# RC522_RFID.net
KiCad netlist of a schematic drawn in Altium Designer
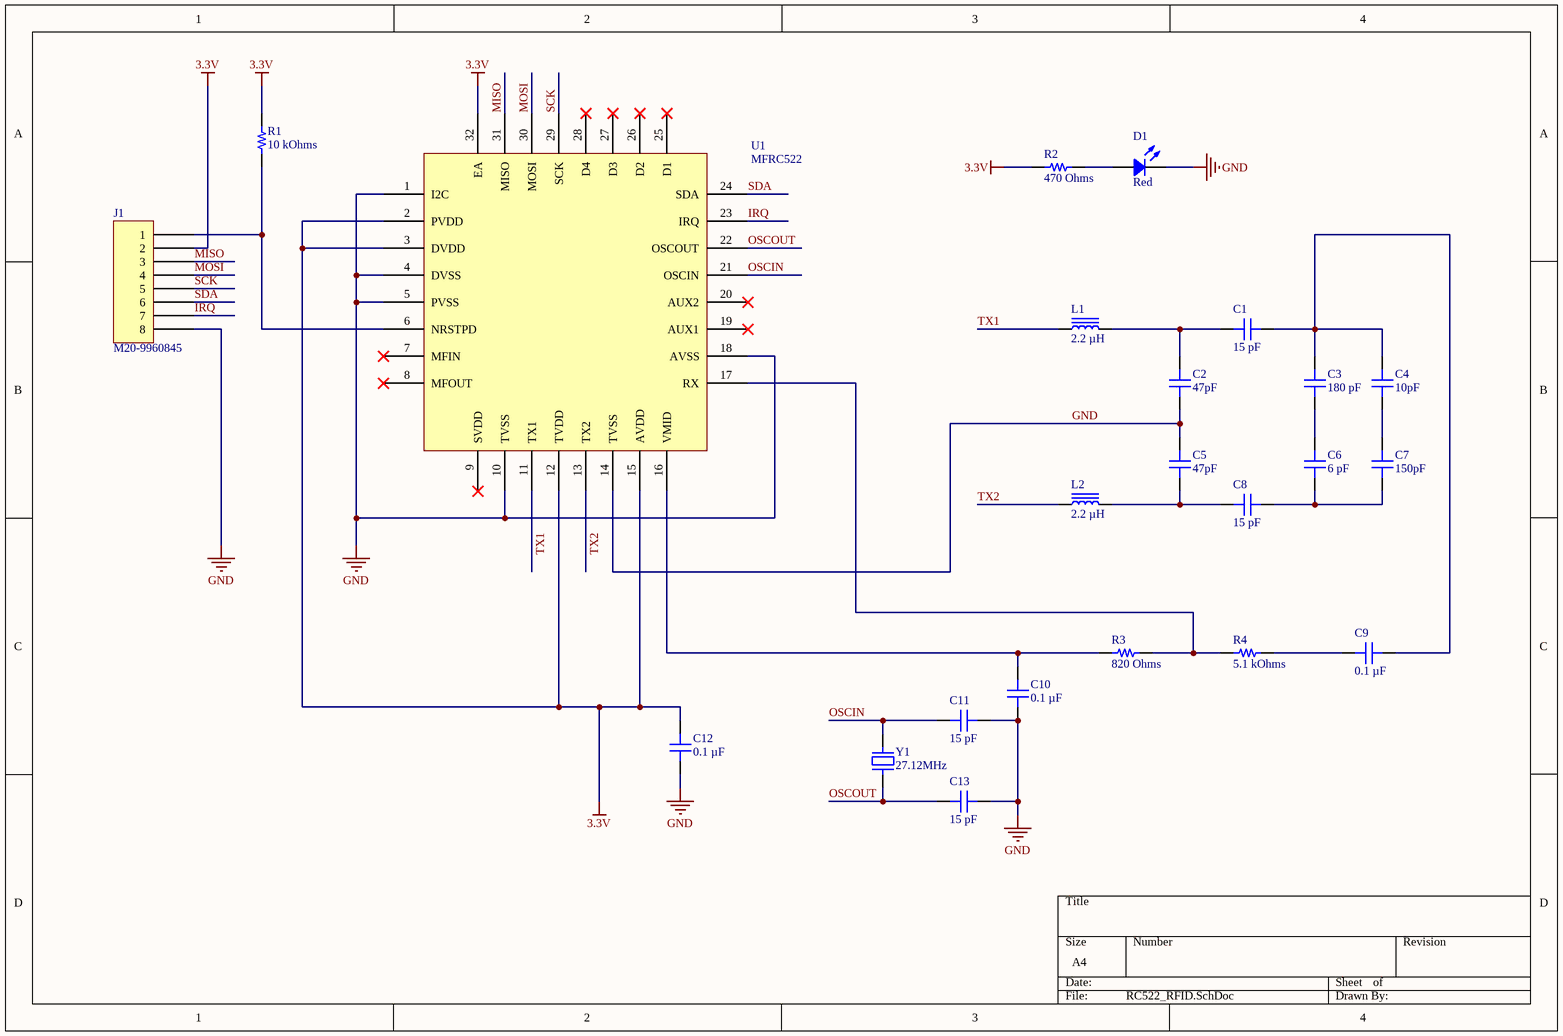
[diagram p0: RC522_RFID.SchDoc]

(export (version "E")
  (design (tool "Eeschema 10.0.6"))
  (components
    (comp (ref "C1")
      (value "15 pF")
      (footprint "CAP 0805_2012")
      (description "CAP CER 15PF 25V C0G/NP0 0805")
      (fields
        (field (name "PART NUMBER") "885012007029")
        (field (name "CAPACITANCE") "15 pF")
        (field (name "MANUFACTURER") "Würth Elektronik")
      )
      (libsource (lib "Celestial Altium Library - altium_library") (part "Capacitor"))
    )
    (comp (ref "C2")
      (value "47pF")
      (footprint "CAP 0805_2012")
      (description "CAP CER 47PF 50V C0G/NP0 0805")
      (fields
        (field (name "PART NUMBER") "08055A470KAT2A")
        (field (name "CAPACITANCE") "47pF")
        (field (name "MANUFACTURER") "AVX Corporation")
      )
      (libsource (lib "Celestial Altium Library - altium_library") (part "Capacitor"))
    )
    (comp (ref "C3")
      (value "180 pF")
      (footprint "CAP 0805_2012")
      (description "CAP CER 180PF 50V X7R 0805")
      (fields
        (field (name "PART NUMBER") "VJ0805Y181KXAPW1BC")
        (field (name "CAPACITANCE") "180 pF")
        (field (name "MANUFACTURER") "Vishay Vitramon")
      )
      (libsource (lib "Celestial Altium Library - altium_library") (part "Capacitor"))
    )
    (comp (ref "C4")
      (value "10pF")
      (footprint "CAP 0805_2012")
      (description "CAP CER 10PF 50V X7R 0805")
      (fields
        (field (name "PART NUMBER") "08055C100KAT2A")
        (field (name "CAPACITANCE") "10pF")
        (field (name "MANUFACTURER") "AVX Corporation")
      )
      (libsource (lib "Celestial Altium Library - altium_library") (part "Capacitor"))
    )
    (comp (ref "C5")
      (value "47pF")
      (footprint "CAP 0805_2012")
      (description "CAP CER 47PF 50V C0G/NP0 0805")
      (fields
        (field (name "PART NUMBER") "08055A470KAT2A")
        (field (name "CAPACITANCE") "47pF")
        (field (name "MANUFACTURER") "AVX Corporation")
      )
      (libsource (lib "Celestial Altium Library - altium_library") (part "Capacitor"))
    )
    (comp (ref "C6")
      (value "6 pF")
      (footprint "CAP 0805_2012")
      (description "CAP CER 6PF 50V C0G/NPO 0805")
      (fields
        (field (name "PART NUMBER") "CC0805DRNPO9BN6R0")
        (field (name "CAPACITANCE") "6 pF")
        (field (name "MANUFACTURER") "Yageo")
      )
      (libsource (lib "Celestial Altium Library - altium_library") (part "Capacitor"))
    )
    (comp (ref "C7")
      (value "150pF")
      (footprint "CAP 0805_2012")
      (description "CAP CER 150PF 50V X7R 0805")
      (fields
        (field (name "PART NUMBER") "08055C151KAT2A")
        (field (name "CAPACITANCE") "150pF")
        (field (name "MANUFACTURER") "AVX Corporation")
      )
      (libsource (lib "Celestial Altium Library - altium_library") (part "Capacitor"))
    )
    (comp (ref "C8")
      (value "15 pF")
      (footprint "CAP 0805_2012")
      (description "CAP CER 15PF 25V C0G/NP0 0805")
      (fields
        (field (name "PART NUMBER") "885012007029")
        (field (name "CAPACITANCE") "15 pF")
        (field (name "MANUFACTURER") "Würth Elektronik")
      )
      (libsource (lib "Celestial Altium Library - altium_library") (part "Capacitor"))
    )
    (comp (ref "C9")
      (value "0.1 µF")
      (footprint "CAP 0805_2012")
      (description "CAP CER 0.1UF 25V X7R 0805")
      (fields
        (field (name "PART NUMBER") "VJ0805Y104KXXCW1BC")
        (field (name "CAPACITANCE") "0.1 µF")
        (field (name "MANUFACTURER") "Vishay Vitramon")
      )
      (libsource (lib "Celestial Altium Library - altium_library") (part "Capacitor"))
    )
    (comp (ref "C10")
      (value "0.1 µF")
      (footprint "CAP 0805_2012")
      (description "CAP CER 0.1UF 25V X7R 0805")
      (fields
        (field (name "PART NUMBER") "VJ0805Y104KXXCW1BC")
        (field (name "CAPACITANCE") "0.1 µF")
        (field (name "MANUFACTURER") "Vishay Vitramon")
      )
      (libsource (lib "Celestial Altium Library - altium_library") (part "Capacitor"))
    )
    (comp (ref "C11")
      (value "15 pF")
      (footprint "CAP 0805_2012")
      (description "CAP CER 15PF 25V C0G/NP0 0805")
      (fields
        (field (name "PART NUMBER") "885012007029")
        (field (name "CAPACITANCE") "15 pF")
        (field (name "MANUFACTURER") "Würth Elektronik")
      )
      (libsource (lib "Celestial Altium Library - altium_library") (part "Capacitor"))
    )
    (comp (ref "C12")
      (value "0.1 µF")
      (footprint "CAP 0805_2012")
      (description "CAP CER 0.1UF 25V X7R 0805")
      (fields
        (field (name "PART NUMBER") "VJ0805Y104KXXCW1BC")
        (field (name "CAPACITANCE") "0.1 µF")
        (field (name "MANUFACTURER") "Vishay Vitramon")
      )
      (libsource (lib "Celestial Altium Library - altium_library") (part "Capacitor"))
    )
    (comp (ref "C13")
      (value "15 pF")
      (footprint "CAP 0805_2012")
      (description "CAP CER 15PF 25V C0G/NP0 0805")
      (fields
        (field (name "PART NUMBER") "885012007029")
        (field (name "CAPACITANCE") "15 pF")
        (field (name "MANUFACTURER") "Würth Elektronik")
      )
      (libsource (lib "Celestial Altium Library - altium_library") (part "Capacitor"))
    )
    (comp (ref "D1")
      (value "Red")
      (footprint "LED 0805_2012 RED")
      (description "LED RED CLEAR 0805 SMD")
      (fields (field (name "PART NUMBER") "5988120107F") (field (name "MANUFACTURER") "Dialight"))
      (libsource (lib "Celestial Altium Library - altium_library") (part "LED"))
    )
    (comp (ref "J1")
      (value "M20-9960845")
      (footprint "HARWIN M20-9960845")
      (description "CONN HEADER R/A 8POS 2.54MM")
      (fields (field (name "MANUFACTURER") "Harwin Inc."))
      (libsource (lib "Celestial Altium Library - altium_library") (part "8 Pin"))
    )
    (comp (ref "L1")
      (value "2.2 µH")
      (footprint "IND 0806_2016")
      (description "FIXED IND 2.2UH 2A 138 MOHM SMD")
      (fields
        (field (name "PART NUMBER") "WPN201610U2R2MTY01")
        (field (name "MANUFACTURER") "Shenzhen Sunlord Electronics Co., Ltd.")
      )
      (libsource (lib "Celestial Altium Library - altium_library") (part "Inductor"))
    )
    (comp (ref "L2")
      (value "2.2 µH")
      (footprint "IND 0806_2016")
      (description "FIXED IND 2.2UH 2A 138 MOHM SMD")
      (fields
        (field (name "PART NUMBER") "WPN201610U2R2MTY01")
        (field (name "MANUFACTURER") "Shenzhen Sunlord Electronics Co., Ltd.")
      )
      (libsource (lib "Celestial Altium Library - altium_library") (part "Inductor"))
    )
    (comp (ref "R1")
      (value "10 kOhms")
      (footprint "RES 0805_2012")
      (description "RES 10K OHM 1% 1/2W 0805")
      (fields (field (name "PART NUMBER") "SDR10EZPF1002") (field (name "MANUFACTURER") "Rohm Semiconductor"))
      (libsource (lib "Celestial Altium Library - altium_library") (part "Resistor"))
    )
    (comp (ref "R2")
      (value "470 Ohms")
      (footprint "YAGEO RES RK73 RS73 SG73 0805_2012")
      (description "RES 470 OHM 1% 1/2W 0805")
      (fields
        (field (name "PART NUMBER") "SG73P2ATTD4700F")
        (field (name "MANUFACTURER") "KOA Speer Electronics, Inc.")
      )
      (libsource (lib "Celestial Altium Library - altium_library") (part "Resistor"))
    )
    (comp (ref "R3")
      (value "820 Ohms")
      (footprint "YAGEO RES 0805_2012")
      (description "RES 820 OHM 1% 1/2W 0805")
      (fields (field (name "PART NUMBER") "SR0805FR-47820RL") (field (name "MANUFACTURER") "Yageo"))
      (libsource (lib "Celestial Altium Library - altium_library") (part "Resistor"))
    )
    (comp (ref "R4")
      (value "5.1 kOhms")
      (footprint "YAGEO RES RK73 RS73 SG73 0805_2012")
      (description "RES 5.1K OHM 1% 1/2W 0805")
      (fields
        (field (name "PART NUMBER") "SG73P2ATTD5101F")
        (field (name "MANUFACTURER") "KOA Speer Electronics, Inc.")
      )
      (libsource (lib "Celestial Altium Library - altium_library") (part "Resistor"))
    )
    (comp (ref "U1") (value "MFRC522") (footprint "MFRC522") (libsource (lib "RC522_RFID") (part "MFRC522")))
    (comp (ref "Y1")
      (value "27.12MHz")
      (footprint "TXC 9C")
      (description "CRYSTAL 27.1200MHZ 18PF SMD")
      (fields (field (name "PART NUMBER") "9C-27.120MAAJ-T") (field (name "MANUFACTURER") "TXC CORPORATION"))
      (libsource (lib "Celestial Altium Library - altium_library") (part "TXC Crystal 9C"))
    )
  )
  (nets
    (net (code "1") (name "/IRQ") (class "Default")
      (node (ref "J1") (pin "7") (pinfunction "7_7") (pintype "passive"))
      (node (ref "U1") (pin "23") (pinfunction "IRQ_23") (pintype "passive"))
    )
    (net (code "2") (name "/MISO") (class "Default")
      (node (ref "J1") (pin "3") (pinfunction "3_3") (pintype "passive"))
      (node (ref "U1") (pin "31") (pinfunction "MISO_31") (pintype "passive"))
    )
    (net (code "3") (name "/MOSI") (class "Default")
      (node (ref "J1") (pin "4") (pinfunction "4_4") (pintype "passive"))
      (node (ref "U1") (pin "30") (pinfunction "MOSI_30") (pintype "passive"))
    )
    (net (code "4") (name "/OSCIN") (class "Default")
      (node (ref "C11") (pin "2") (pinfunction "2_2") (pintype "passive"))
      (node (ref "U1") (pin "21") (pinfunction "OSCIN_21") (pintype "passive"))
      (node (ref "Y1") (pin "2") (pinfunction "2_2") (pintype "passive"))
    )
    (net (code "5") (name "/OSCOUT") (class "Default")
      (node (ref "C13") (pin "1") (pinfunction "1_1") (pintype "passive"))
      (node (ref "U1") (pin "22") (pinfunction "OSCOUT_22") (pintype "passive"))
      (node (ref "Y1") (pin "1") (pinfunction "1_1") (pintype "passive"))
    )
    (net (code "6") (name "/SCK") (class "Default")
      (node (ref "J1") (pin "5") (pinfunction "5_5") (pintype "passive"))
      (node (ref "U1") (pin "29") (pinfunction "SCK_29") (pintype "passive"))
    )
    (net (code "7") (name "/SDA") (class "Default")
      (node (ref "J1") (pin "6") (pinfunction "6_6") (pintype "passive"))
      (node (ref "U1") (pin "24") (pinfunction "SDA_24") (pintype "passive"))
    )
    (net (code "8") (name "/TX1") (class "Default")
      (node (ref "L1") (pin "1") (pinfunction "1_1") (pintype "passive"))
      (node (ref "U1") (pin "11") (pinfunction "TX1_11") (pintype "passive"))
    )
    (net (code "9") (name "/TX2") (class "Default")
      (node (ref "L2") (pin "1") (pinfunction "1_1") (pintype "passive"))
      (node (ref "U1") (pin "13") (pinfunction "TX2_13") (pintype "passive"))
    )
    (net (code "10") (name "3.3V") (class "Default")
      (node (ref "C12") (pin "2") (pinfunction "2_2") (pintype "passive"))
      (node (ref "J1") (pin "2") (pinfunction "2_2") (pintype "passive"))
      (node (ref "R1") (pin "1") (pinfunction "1_1") (pintype "passive"))
      (node (ref "R2") (pin "1") (pinfunction "1_1") (pintype "passive"))
      (node (ref "U1") (pin "12") (pinfunction "TVDD_12") (pintype "passive"))
      (node (ref "U1") (pin "15") (pinfunction "AVDD_15") (pintype "passive"))
      (node (ref "U1") (pin "2") (pinfunction "PVDD_2") (pintype "passive"))
      (node (ref "U1") (pin "3") (pinfunction "DVDD_3") (pintype "passive"))
      (node (ref "U1") (pin "32") (pinfunction "EA_32") (pintype "passive"))
    )
    (net (code "11") (name "GND") (class "Default")
      (node (ref "C10") (pin "1") (pinfunction "1_1") (pintype "passive"))
      (node (ref "C11") (pin "1") (pinfunction "1_1") (pintype "passive"))
      (node (ref "C12") (pin "1") (pinfunction "1_1") (pintype "passive"))
      (node (ref "C13") (pin "2") (pinfunction "2_2") (pintype "passive"))
      (node (ref "C2") (pin "1") (pinfunction "1_1") (pintype "passive"))
      (node (ref "C5") (pin "2") (pinfunction "2_2") (pintype "passive"))
      (node (ref "D1") (pin "2") (pinfunction "2_2") (pintype "passive"))
      (node (ref "J1") (pin "8") (pinfunction "8_8") (pintype "passive"))
      (node (ref "U1") (pin "1") (pinfunction "I2C_1") (pintype "passive"))
      (node (ref "U1") (pin "10") (pinfunction "TVSS_10") (pintype "passive"))
      (node (ref "U1") (pin "14") (pinfunction "TVSS_14") (pintype "passive"))
      (node (ref "U1") (pin "18") (pinfunction "AVSS_18") (pintype "passive"))
      (node (ref "U1") (pin "4") (pinfunction "DVSS_4") (pintype "passive"))
      (node (ref "U1") (pin "5") (pinfunction "PVSS_5") (pintype "passive"))
    )
    (net (code "12") (name "Net-(C1-Pad1)") (class "Default")
      (node (ref "C1") (pin "1") (pinfunction "1_1") (pintype "passive"))
      (node (ref "C2") (pin "2") (pinfunction "2_2") (pintype "passive"))
      (node (ref "L1") (pin "2") (pinfunction "2_2") (pintype "passive"))
    )
    (net (code "13") (name "Net-(C1-Pad2)") (class "Default")
      (node (ref "C1") (pin "2") (pinfunction "2_2") (pintype "passive"))
      (node (ref "C3") (pin "2") (pinfunction "2_2") (pintype "passive"))
      (node (ref "C4") (pin "2") (pinfunction "2_2") (pintype "passive"))
      (node (ref "C9") (pin "2") (pinfunction "2_2") (pintype "passive"))
    )
    (net (code "14") (name "Net-(C3-Pad1)") (class "Default")
      (node (ref "C3") (pin "1") (pinfunction "1_1") (pintype "passive"))
      (node (ref "C6") (pin "2") (pinfunction "2_2") (pintype "passive"))
    )
    (net (code "15") (name "Net-(C4-Pad1)") (class "Default")
      (node (ref "C4") (pin "1") (pinfunction "1_1") (pintype "passive"))
      (node (ref "C7") (pin "2") (pinfunction "2_2") (pintype "passive"))
    )
    (net (code "16") (name "Net-(C5-Pad1)") (class "Default")
      (node (ref "C5") (pin "1") (pinfunction "1_1") (pintype "passive"))
      (node (ref "C8") (pin "1") (pinfunction "1_1") (pintype "passive"))
      (node (ref "L2") (pin "2") (pinfunction "2_2") (pintype "passive"))
    )
    (net (code "17") (name "Net-(C6-Pad1)") (class "Default")
      (node (ref "C6") (pin "1") (pinfunction "1_1") (pintype "passive"))
      (node (ref "C7") (pin "1") (pinfunction "1_1") (pintype "passive"))
      (node (ref "C8") (pin "2") (pinfunction "2_2") (pintype "passive"))
    )
    (net (code "18") (name "Net-(C9-Pad1)") (class "Default")
      (node (ref "C9") (pin "1") (pinfunction "1_1") (pintype "passive"))
      (node (ref "R4") (pin "2") (pinfunction "2_2") (pintype "passive"))
    )
    (net (code "19") (name "Net-(D1-Pad1)") (class "Default")
      (node (ref "D1") (pin "1") (pinfunction "1_1") (pintype "passive"))
      (node (ref "R2") (pin "2") (pinfunction "2_2") (pintype "passive"))
    )
    (net (code "20") (name "Net-(U1-NRSTPD)") (class "Default")
      (node (ref "J1") (pin "1") (pinfunction "1_1") (pintype "passive"))
      (node (ref "R1") (pin "2") (pinfunction "2_2") (pintype "passive"))
      (node (ref "U1") (pin "6") (pinfunction "NRSTPD_6") (pintype "passive"))
    )
    (net (code "21") (name "Net-(U1-RX)") (class "Default")
      (node (ref "R3") (pin "2") (pinfunction "2_2") (pintype "passive"))
      (node (ref "R4") (pin "1") (pinfunction "1_1") (pintype "passive"))
      (node (ref "U1") (pin "17") (pinfunction "RX_17") (pintype "passive"))
    )
    (net (code "22") (name "Net-(U1-VMID)") (class "Default")
      (node (ref "C10") (pin "2") (pinfunction "2_2") (pintype "passive"))
      (node (ref "R3") (pin "1") (pinfunction "1_1") (pintype "passive"))
      (node (ref "U1") (pin "16") (pinfunction "VMID_16") (pintype "passive"))
    )
    (net (code "23") (name "unconnected-(U1-AUX1-Pad19)") (class "Default")
      (node (ref "U1") (pin "19") (pinfunction "AUX1_19") (pintype "passive+no_connect"))
    )
    (net (code "24") (name "unconnected-(U1-AUX2-Pad20)") (class "Default")
      (node (ref "U1") (pin "20") (pinfunction "AUX2_20") (pintype "passive+no_connect"))
    )
    (net (code "25") (name "unconnected-(U1-D1-Pad25)") (class "Default")
      (node (ref "U1") (pin "25") (pinfunction "D1_25") (pintype "passive+no_connect"))
    )
    (net (code "26") (name "unconnected-(U1-D2-Pad26)") (class "Default")
      (node (ref "U1") (pin "26") (pinfunction "D2_26") (pintype "passive+no_connect"))
    )
    (net (code "27") (name "unconnected-(U1-D3-Pad27)") (class "Default")
      (node (ref "U1") (pin "27") (pinfunction "D3_27") (pintype "passive+no_connect"))
    )
    (net (code "28") (name "unconnected-(U1-D4-Pad28)") (class "Default")
      (node (ref "U1") (pin "28") (pinfunction "D4_28") (pintype "passive+no_connect"))
    )
    (net (code "29") (name "unconnected-(U1-MFIN-Pad7)") (class "Default")
      (node (ref "U1") (pin "7") (pinfunction "MFIN_7") (pintype "passive+no_connect"))
    )
    (net (code "30") (name "unconnected-(U1-MFOUT-Pad8)") (class "Default")
      (node (ref "U1") (pin "8") (pinfunction "MFOUT_8") (pintype "passive+no_connect"))
    )
    (net (code "31") (name "unconnected-(U1-SVDD-Pad9)") (class "Default")
      (node (ref "U1") (pin "9") (pinfunction "SVDD_9") (pintype "passive+no_connect"))
    )
  )
)
